# STM32Fx.net
KiCad netlist of a schematic drawn in Altium Designer
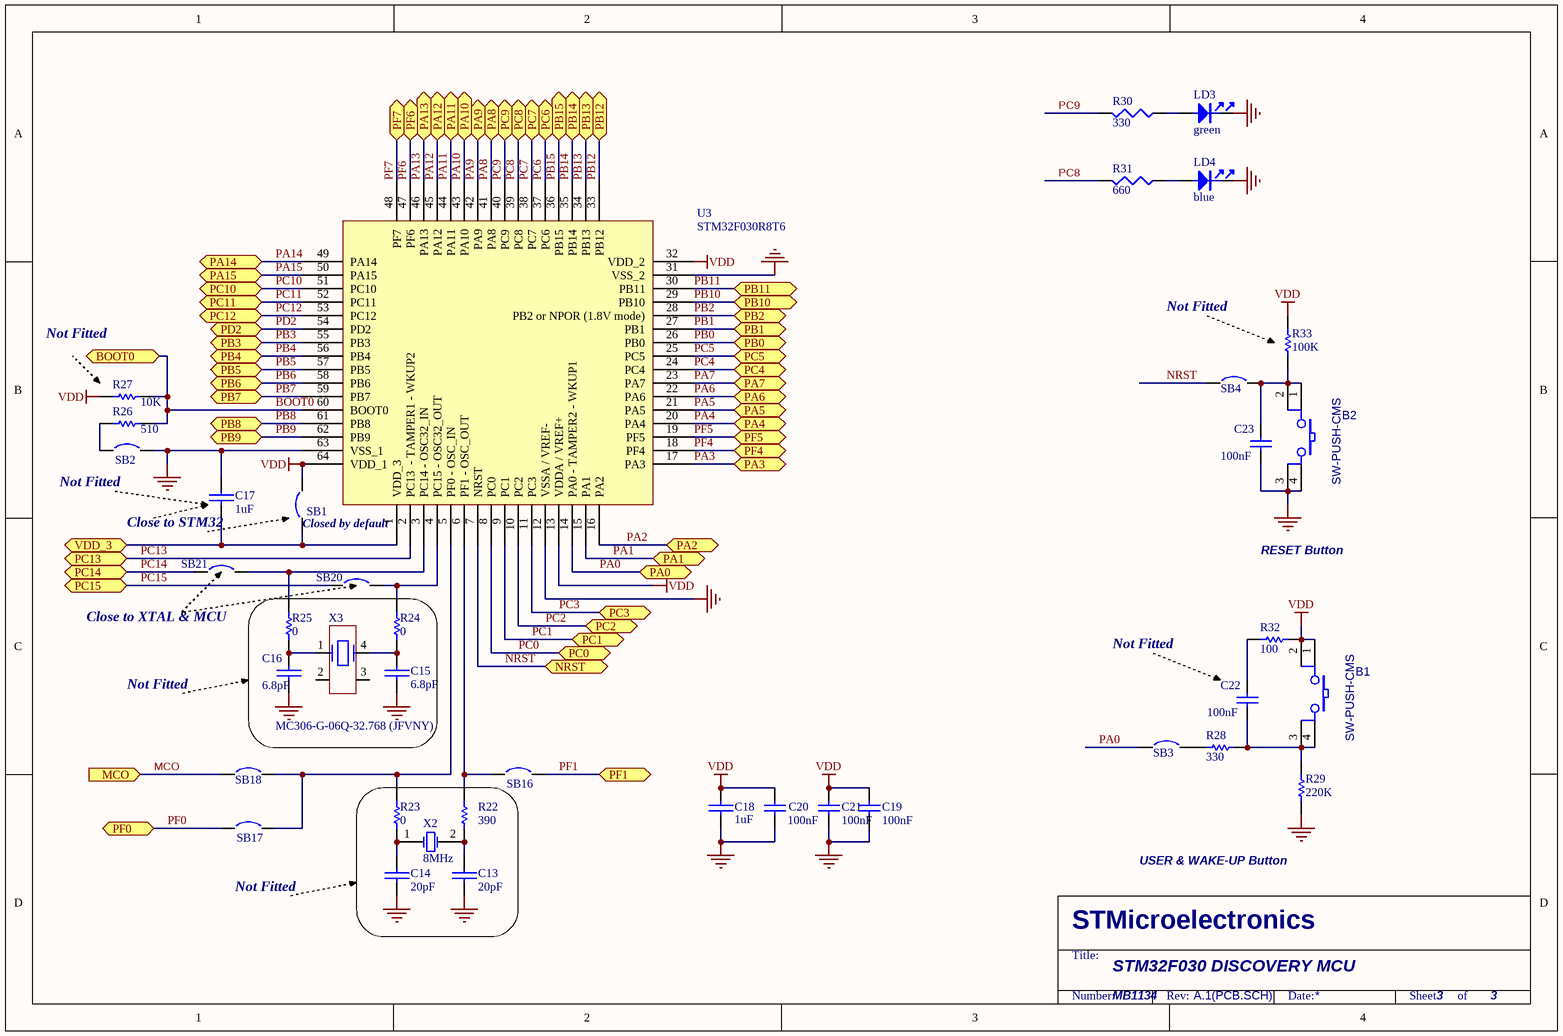
[diagram p0: STM32Fx.SchDoc]

(export (version "E")
  (design (tool "Eeschema 10.0.6"))
  (components
    (comp (ref "B1")
      (value "SW-PUSH-CMS")
      (footprint "BP1CMS")
      (description "Non-Open Push-Button 0.1A 24V")
      (libsource (lib "MB1034") (part "SW-PUSH-CMS"))
    )
    (comp (ref "B2")
      (value "SW-PUSH-CMS")
      (footprint "BP1CMS")
      (description "Non-Open Push-Button 0.1A 24V")
      (libsource (lib "MB1034") (part "SW-PUSH-CMS"))
    )
    (comp (ref "C13")
      (value "20pF")
      (footprint "0603C")
      (description "Capacitor")
      (libsource (lib "*") (part "CAP"))
    )
    (comp (ref "C14")
      (value "20pF")
      (footprint "0603C")
      (description "Capacitor")
      (libsource (lib "*") (part "CAP"))
    )
    (comp (ref "C15")
      (value "6.8pF")
      (footprint "0603C")
      (description "Capacitor")
      (libsource (lib "") (part "CAP_1"))
    )
    (comp (ref "C16")
      (value "6.8pF")
      (footprint "0603C")
      (description "Capacitor")
      (libsource (lib "") (part "CAP_1"))
    )
    (comp (ref "C17")
      (value "1uF")
      (footprint "0603C")
      (description "Capacitor")
      (libsource (lib "*") (part "CAP"))
    )
    (comp (ref "C18")
      (value "1uF")
      (footprint "0603C")
      (description "Capacitor")
      (libsource (lib "*") (part "CAP"))
    )
    (comp (ref "C19")
      (value "100nF")
      (footprint "0603C")
      (description "Capacitor")
      (fields (field (name "PUBLISHER") "Altium Limited"))
      (libsource (lib "Miscellaneous Devices") (part "Cap"))
    )
    (comp (ref "C20")
      (value "100nF")
      (footprint "0603C")
      (description "Capacitor")
      (fields (field (name "PUBLISHER") "Altium Limited"))
      (libsource (lib "Miscellaneous Devices") (part "Cap"))
    )
    (comp (ref "C21")
      (value "100nF")
      (footprint "0603C")
      (description "Capacitor")
      (fields (field (name "PUBLISHER") "Altium Limited"))
      (libsource (lib "Miscellaneous Devices") (part "Cap"))
    )
    (comp (ref "C22")
      (value "100nF")
      (footprint "0603C")
      (description "Capacitor")
      (fields (field (name "PUBLISHER") "Altium Limited"))
      (libsource (lib "Miscellaneous Devices") (part "CAP"))
    )
    (comp (ref "C23")
      (value "100nF")
      (footprint "0603C")
      (description "Capacitor")
      (fields (field (name "PUBLISHER") "Altium Limited"))
      (libsource (lib "Miscellaneous Devices") (part "CAP"))
    )
    (comp (ref "LD3") (value "green") (footprint "0603D") (libsource (lib "*") (part "PHOTO")))
    (comp (ref "LD4") (value "blue") (footprint "0603D") (libsource (lib "*") (part "PHOTO")))
    (comp (ref "R22")
      (value "390")
      (footprint "0603R")
      (description "Resistor")
      (fields (field (name "PUBLISHER") "Altium Limited"))
      (libsource (lib "Miscellaneous Devices") (part "Res1"))
    )
    (comp (ref "R23")
      (value "0")
      (footprint "0603R-GS")
      (description "Resistor")
      (fields (field (name "PUBLISHER") "Altium Limited"))
      (libsource (lib "Miscellaneous Devices") (part "Res1"))
    )
    (comp (ref "R24")
      (value "0")
      (footprint "0603R-GS")
      (description "Resistor")
      (fields (field (name "PUBLISHER") "Altium Limited"))
      (libsource (lib "Miscellaneous Devices") (part "Res1"))
    )
    (comp (ref "R25")
      (value "0")
      (footprint "0603R-GS")
      (description "Resistor")
      (fields (field (name "PUBLISHER") "Altium Limited"))
      (libsource (lib "Miscellaneous Devices") (part "Res1"))
    )
    (comp (ref "R26")
      (value "510")
      (footprint "0603R")
      (description "Resistor")
      (fields (field (name "PUBLISHER") "Altium Limited"))
      (libsource (lib "Miscellaneous Devices") (part "Res1"))
    )
    (comp (ref "R27")
      (value "10K")
      (footprint "0603R")
      (description "Resistor")
      (fields (field (name "PUBLISHER") "Altium Limited"))
      (libsource (lib "Miscellaneous Devices") (part "res1"))
    )
    (comp (ref "R28")
      (value "330")
      (footprint "0402R")
      (description "Resistor")
      (fields (field (name "PUBLISHER") "Altium Limited"))
      (libsource (lib "Miscellaneous Devices") (part "res1"))
    )
    (comp (ref "R29")
      (value "220K")
      (description "Resistor")
      (fields (field (name "PUBLISHER") "Altium Limited"))
      (libsource (lib "Miscellaneous Devices") (part "res1"))
    )
    (comp (ref "R30") (value "330") (footprint "0603R") (libsource (lib "*") (part "RES1")))
    (comp (ref "R31") (value "660") (footprint "0603R") (libsource (lib "*") (part "RES1")))
    (comp (ref "R32")
      (value "100")
      (footprint "0402R")
      (description "Resistor")
      (fields (field (name "PUBLISHER") "Altium Limited"))
      (libsource (lib "Miscellaneous Devices") (part "res1"))
    )
    (comp (ref "R33")
      (value "100K")
      (footprint "0402R")
      (description "Resistor")
      (fields (field (name "PUBLISHER") "Altium Limited"))
      (libsource (lib "Miscellaneous Devices") (part "res1"))
    )
    (comp (ref "SB1")
      (value "Circuit Breaker")
      (footprint "JP2_SMD")
      (fields (field (name "PUBLISHER") "Altium Limited"))
      (libsource (lib "MB915") (part "Circuit Breaker"))
    )
    (comp (ref "SB2")
      (value "Circuit Breaker")
      (footprint "JP2_SMD")
      (fields (field (name "PUBLISHER") "Altium Limited"))
      (libsource (lib "MB915") (part "Circuit Breaker"))
    )
    (comp (ref "SB3")
      (value "Circuit Breaker")
      (footprint "JP2_SMD")
      (fields (field (name "PUBLISHER") "Altium Limited"))
      (libsource (lib "MB915") (part "Circuit Breaker"))
    )
    (comp (ref "SB4")
      (value "Circuit Breaker")
      (footprint "JP2_SMD")
      (fields (field (name "PUBLISHER") "Altium Limited"))
      (libsource (lib "MB915") (part "Circuit Breaker"))
    )
    (comp (ref "SB16")
      (value "Circuit Breaker")
      (footprint "JP2_SMD")
      (fields (field (name "PUBLISHER") "Altium Limited"))
      (libsource (lib "MB915") (part "Circuit Breaker"))
    )
    (comp (ref "SB17")
      (value "Circuit Breaker")
      (footprint "JP2_SMD")
      (fields (field (name "PUBLISHER") "Altium Limited"))
      (libsource (lib "MB915") (part "Circuit Breaker"))
    )
    (comp (ref "SB18")
      (value "Circuit Breaker")
      (footprint "JP2_SMD")
      (fields (field (name "PUBLISHER") "Altium Limited"))
      (libsource (lib "MB915") (part "Circuit Breaker"))
    )
    (comp (ref "SB20")
      (value "Circuit Breaker")
      (footprint "JP2_SMD")
      (fields (field (name "PUBLISHER") "Altium Limited"))
      (libsource (lib "MB915") (part "Circuit Breaker"))
    )
    (comp (ref "SB21")
      (value "Circuit Breaker")
      (footprint "JP2_SMD")
      (fields (field (name "PUBLISHER") "Altium Limited"))
      (libsource (lib "MB915") (part "Circuit Breaker"))
    )
    (comp (ref "U3")
      (value "STM32F030R8T6")
      (footprint "LQFP64")
      (description "Advanced ARM based 32-bit Cortex?M0 MCU with 64 Kbytes Flash and 8 Kbytes of SRAM")
      (libsource (lib "MB1134") (part "STM32F030R8T6"))
    )
    (comp (ref "X2")
      (value "8MHz")
      (footprint "XTAL1")
      (description "Crystal Oscillator")
      (fields (field (name "PUBLISHER") "Altium Limited"))
      (libsource (lib "MCD_TOOLS") (part "XTAL"))
    )
    (comp (ref "X3")
      (value "MC306-G-06Q-32.768 (JFVNY)")
      (footprint "MC306-CRYSTAL")
      (libsource (lib "*") (part "MC306"))
    )
  )
  (nets
    (net (code "1") (name "/BOOT0") (class "Default")
      (node (ref "R26") (pin "2") (pinfunction "2_2") (pintype "passive"))
      (node (ref "R27") (pin "2") (pinfunction "2_2") (pintype "passive"))
      (node (ref "U3") (pin "60") (pinfunction "BOOT0_60") (pintype "passive"))
    )
    (net (code "2") (name "/MCO") (class "Default")
      (node (ref "SB18") (pin "1") (pinfunction "1_1") (pintype "passive"))
    )
    (net (code "3") (name "/NRST") (class "Default")
      (node (ref "SB4") (pin "1") (pinfunction "1_1") (pintype "passive"))
      (node (ref "U3") (pin "7") (pinfunction "NRST_7") (pintype "passive"))
    )
    (net (code "4") (name "/PA0") (class "Default")
      (node (ref "SB3") (pin "1") (pinfunction "1_1") (pintype "passive"))
      (node (ref "U3") (pin "14") (pinfunction "PA0_-_TAMPER2_-_WKUP1_14") (pintype "passive"))
    )
    (net (code "5") (name "/PA1") (class "Default")
      (node (ref "U3") (pin "15") (pinfunction "PA1_15") (pintype "passive"))
    )
    (net (code "6") (name "/PA2") (class "Default")
      (node (ref "U3") (pin "16") (pinfunction "PA2_16") (pintype "passive"))
    )
    (net (code "7") (name "/PA3") (class "Default")
      (node (ref "U3") (pin "17") (pinfunction "PA3_17") (pintype "passive"))
    )
    (net (code "8") (name "/PA4") (class "Default")
      (node (ref "U3") (pin "20") (pinfunction "PA4_20") (pintype "passive"))
    )
    (net (code "9") (name "/PA5") (class "Default")
      (node (ref "U3") (pin "21") (pinfunction "PA5_21") (pintype "passive"))
    )
    (net (code "10") (name "/PA6") (class "Default")
      (node (ref "U3") (pin "22") (pinfunction "PA6_22") (pintype "passive"))
    )
    (net (code "11") (name "/PA7") (class "Default")
      (node (ref "U3") (pin "23") (pinfunction "PA7_23") (pintype "passive"))
    )
    (net (code "12") (name "/PA8") (class "Default")
      (node (ref "U3") (pin "41") (pinfunction "PA8_41") (pintype "passive"))
    )
    (net (code "13") (name "/PA9") (class "Default")
      (node (ref "U3") (pin "42") (pinfunction "PA9_42") (pintype "passive"))
    )
    (net (code "14") (name "/PA10") (class "Default")
      (node (ref "U3") (pin "43") (pinfunction "PA10_43") (pintype "passive"))
    )
    (net (code "15") (name "/PA11") (class "Default")
      (node (ref "U3") (pin "44") (pinfunction "PA11_44") (pintype "passive"))
    )
    (net (code "16") (name "/PA12") (class "Default")
      (node (ref "U3") (pin "45") (pinfunction "PA12_45") (pintype "passive"))
    )
    (net (code "17") (name "/PA13") (class "Default")
      (node (ref "U3") (pin "46") (pinfunction "PA13_46") (pintype "passive"))
    )
    (net (code "18") (name "/PA14") (class "Default")
      (node (ref "U3") (pin "49") (pinfunction "PA14_49") (pintype "passive"))
    )
    (net (code "19") (name "/PA15") (class "Default")
      (node (ref "U3") (pin "50") (pinfunction "PA15_50") (pintype "passive"))
    )
    (net (code "20") (name "/PB0") (class "Default")
      (node (ref "U3") (pin "26") (pinfunction "PB0_26") (pintype "passive"))
    )
    (net (code "21") (name "/PB1") (class "Default")
      (node (ref "U3") (pin "27") (pinfunction "PB1_27") (pintype "passive"))
    )
    (net (code "22") (name "/PB2") (class "Default")
      (node (ref "U3") (pin "28") (pinfunction "PB2_or_NPOR_(1.8V_mode)_28") (pintype "passive"))
    )
    (net (code "23") (name "/PB3") (class "Default")
      (node (ref "U3") (pin "55") (pinfunction "PB3_55") (pintype "passive"))
    )
    (net (code "24") (name "/PB4") (class "Default")
      (node (ref "U3") (pin "56") (pinfunction "PB4_56") (pintype "passive"))
    )
    (net (code "25") (name "/PB5") (class "Default")
      (node (ref "U3") (pin "57") (pinfunction "PB5_57") (pintype "passive"))
    )
    (net (code "26") (name "/PB6") (class "Default")
      (node (ref "U3") (pin "58") (pinfunction "PB6_58") (pintype "passive"))
    )
    (net (code "27") (name "/PB7") (class "Default")
      (node (ref "U3") (pin "59") (pinfunction "PB7_59") (pintype "passive"))
    )
    (net (code "28") (name "/PB8") (class "Default")
      (node (ref "U3") (pin "61") (pinfunction "PB8_61") (pintype "passive"))
    )
    (net (code "29") (name "/PB9") (class "Default")
      (node (ref "U3") (pin "62") (pinfunction "PB9_62") (pintype "passive"))
    )
    (net (code "30") (name "/PB10") (class "Default")
      (node (ref "U3") (pin "29") (pinfunction "PB10_29") (pintype "passive"))
    )
    (net (code "31") (name "/PB11") (class "Default")
      (node (ref "U3") (pin "30") (pinfunction "PB11_30") (pintype "passive"))
    )
    (net (code "32") (name "/PB12") (class "Default")
      (node (ref "U3") (pin "33") (pinfunction "PB12_33") (pintype "passive"))
    )
    (net (code "33") (name "/PB13") (class "Default")
      (node (ref "U3") (pin "34") (pinfunction "PB13_34") (pintype "passive"))
    )
    (net (code "34") (name "/PB14") (class "Default")
      (node (ref "U3") (pin "35") (pinfunction "PB14_35") (pintype "passive"))
    )
    (net (code "35") (name "/PB15") (class "Default")
      (node (ref "U3") (pin "36") (pinfunction "PB15_36") (pintype "passive"))
    )
    (net (code "36") (name "/PC0") (class "Default")
      (node (ref "U3") (pin "8") (pinfunction "PC0_8") (pintype "passive"))
    )
    (net (code "37") (name "/PC1") (class "Default")
      (node (ref "U3") (pin "9") (pinfunction "PC1_9") (pintype "passive"))
    )
    (net (code "38") (name "/PC2") (class "Default")
      (node (ref "U3") (pin "10") (pinfunction "PC2_10") (pintype "passive"))
    )
    (net (code "39") (name "/PC3") (class "Default")
      (node (ref "U3") (pin "11") (pinfunction "PC3_11") (pintype "passive"))
    )
    (net (code "40") (name "/PC4") (class "Default")
      (node (ref "U3") (pin "24") (pinfunction "PC4_24") (pintype "passive"))
    )
    (net (code "41") (name "/PC5") (class "Default")
      (node (ref "U3") (pin "25") (pinfunction "PC5_25") (pintype "passive"))
    )
    (net (code "42") (name "/PC6") (class "Default")
      (node (ref "U3") (pin "37") (pinfunction "PC6_37") (pintype "passive"))
    )
    (net (code "43") (name "/PC7") (class "Default")
      (node (ref "U3") (pin "38") (pinfunction "PC7_38") (pintype "passive"))
    )
    (net (code "44") (name "/PC8") (class "Default")
      (node (ref "R31") (pin "2") (pinfunction "2_2") (pintype "passive"))
      (node (ref "U3") (pin "39") (pinfunction "PC8_39") (pintype "passive"))
    )
    (net (code "45") (name "/PC9") (class "Default")
      (node (ref "R30") (pin "2") (pinfunction "2_2") (pintype "passive"))
      (node (ref "U3") (pin "40") (pinfunction "PC9_40") (pintype "passive"))
    )
    (net (code "46") (name "/PC10") (class "Default")
      (node (ref "U3") (pin "51") (pinfunction "PC10_51") (pintype "passive"))
    )
    (net (code "47") (name "/PC11") (class "Default")
      (node (ref "U3") (pin "52") (pinfunction "PC11_52") (pintype "passive"))
    )
    (net (code "48") (name "/PC12") (class "Default")
      (node (ref "U3") (pin "53") (pinfunction "PC12_53") (pintype "passive"))
    )
    (net (code "49") (name "/PC13") (class "Default")
      (node (ref "U3") (pin "2") (pinfunction "PC13__-_TAMPER1_-_WKUP2_2") (pintype "passive"))
    )
    (net (code "50") (name "/PC14") (class "Default")
      (node (ref "SB21") (pin "1") (pinfunction "1_1") (pintype "passive"))
    )
    (net (code "51") (name "/PC15") (class "Default")
      (node (ref "SB20") (pin "1") (pinfunction "1_1") (pintype "passive"))
    )
    (net (code "52") (name "/PD2") (class "Default")
      (node (ref "U3") (pin "54") (pinfunction "PD2_54") (pintype "passive"))
    )
    (net (code "53") (name "/PF0") (class "Default")
      (node (ref "SB17") (pin "1") (pinfunction "1_1") (pintype "passive"))
    )
    (net (code "54") (name "/PF1") (class "Default")
      (node (ref "SB16") (pin "2") (pinfunction "2_2") (pintype "passive"))
    )
    (net (code "55") (name "/PF4") (class "Default")
      (node (ref "U3") (pin "18") (pinfunction "PF4_18") (pintype "passive"))
    )
    (net (code "56") (name "/PF5") (class "Default")
      (node (ref "U3") (pin "19") (pinfunction "PF5_19") (pintype "passive"))
    )
    (net (code "57") (name "/PF6") (class "Default")
      (node (ref "U3") (pin "47") (pinfunction "PF6_47") (pintype "passive"))
    )
    (net (code "58") (name "/PF7") (class "Default")
      (node (ref "U3") (pin "48") (pinfunction "PF7_48") (pintype "passive"))
    )
    (net (code "59") (name "/VDD_3") (class "Default")
      (node (ref "C17") (pin "2") (pinfunction "2_2") (pintype "passive"))
      (node (ref "SB1") (pin "1") (pinfunction "1_1") (pintype "passive"))
      (node (ref "U3") (pin "1") (pinfunction "VDD_3_1") (pintype "passive"))
    )
    (net (code "60") (name "GND") (class "Default")
      (node (ref "B2") (pin "3") (pinfunction "3_3") (pintype "passive"))
      (node (ref "B2") (pin "4") (pinfunction "4_4") (pintype "passive"))
      (node (ref "C13") (pin "2") (pinfunction "2_2") (pintype "passive"))
      (node (ref "C14") (pin "2") (pinfunction "2_2") (pintype "passive"))
      (node (ref "C15") (pin "2") (pinfunction "2_2") (pintype "passive"))
      (node (ref "C16") (pin "2") (pinfunction "2_2") (pintype "passive"))
      (node (ref "C17") (pin "1") (pinfunction "1_1") (pintype "passive"))
      (node (ref "C18") (pin "2") (pinfunction "2_2") (pintype "passive"))
      (node (ref "C19") (pin "2") (pinfunction "2_2") (pintype "passive"))
      (node (ref "C20") (pin "2") (pinfunction "2_2") (pintype "passive"))
      (node (ref "C21") (pin "2") (pinfunction "2_2") (pintype "passive"))
      (node (ref "C23") (pin "1") (pinfunction "1_1") (pintype "passive"))
      (node (ref "LD3") (pin "2") (pintype "passive"))
      (node (ref "LD4") (pin "2") (pintype "passive"))
      (node (ref "R29") (pin "1") (pinfunction "1_1") (pintype "passive"))
      (node (ref "SB2") (pin "2") (pinfunction "2_2") (pintype "passive"))
      (node (ref "U3") (pin "12") (pinfunction "VSSA_/_VREF-_12") (pintype "passive"))
      (node (ref "U3") (pin "31") (pinfunction "VSS_2_31") (pintype "passive"))
      (node (ref "U3") (pin "63") (pinfunction "VSS_1_63") (pintype "passive"))
    )
    (net (code "61") (name "Net-(B1-Pad3)") (class "Default")
      (node (ref "B1") (pin "3") (pinfunction "3_3") (pintype "passive"))
      (node (ref "B1") (pin "4") (pinfunction "4_4") (pintype "passive"))
      (node (ref "C22") (pin "1") (pinfunction "1_1") (pintype "passive"))
      (node (ref "R28") (pin "2") (pinfunction "2_2") (pintype "passive"))
      (node (ref "R29") (pin "2") (pinfunction "2_2") (pintype "passive"))
    )
    (net (code "62") (name "Net-(B2-Pad1)") (class "Default")
      (node (ref "B2") (pin "1") (pinfunction "1_1") (pintype "passive"))
      (node (ref "B2") (pin "2") (pinfunction "2_2") (pintype "passive"))
      (node (ref "C23") (pin "2") (pinfunction "2_2") (pintype "passive"))
      (node (ref "R33") (pin "1") (pinfunction "1_1") (pintype "passive"))
      (node (ref "SB4") (pin "2") (pinfunction "2_2") (pintype "passive"))
    )
    (net (code "63") (name "Net-(C15-Pad1)") (class "Default")
      (node (ref "C15") (pin "1") (pinfunction "1_1") (pintype "passive"))
      (node (ref "R24") (pin "1") (pinfunction "1_1") (pintype "passive"))
      (node (ref "X3") (pin "4") (pinfunction "4_4") (pintype "passive"))
    )
    (net (code "64") (name "Net-(C16-Pad1)") (class "Default")
      (node (ref "C16") (pin "1") (pinfunction "1_1") (pintype "passive"))
      (node (ref "R25") (pin "1") (pinfunction "1_1") (pintype "passive"))
      (node (ref "X3") (pin "1") (pinfunction "1_1") (pintype "passive"))
    )
    (net (code "65") (name "Net-(C22-Pad2)") (class "Default")
      (node (ref "C22") (pin "2") (pinfunction "2_2") (pintype "passive"))
      (node (ref "R32") (pin "1") (pinfunction "1_1") (pintype "passive"))
    )
    (net (code "66") (name "Net-(LD3-Pad1)") (class "Default")
      (node (ref "LD3") (pin "1") (pintype "passive"))
      (node (ref "R30") (pin "1") (pinfunction "1_1") (pintype "passive"))
    )
    (net (code "67") (name "Net-(LD4-Pad1)") (class "Default")
      (node (ref "LD4") (pin "1") (pintype "passive"))
      (node (ref "R31") (pin "1") (pinfunction "1_1") (pintype "passive"))
    )
    (net (code "68") (name "Net-(R26-Pad1)") (class "Default")
      (node (ref "R26") (pin "1") (pinfunction "1_1") (pintype "passive"))
      (node (ref "SB2") (pin "1") (pinfunction "1_1") (pintype "passive"))
    )
    (net (code "69") (name "Net-(R28-Pad1)") (class "Default")
      (node (ref "R28") (pin "1") (pinfunction "1_1") (pintype "passive"))
      (node (ref "SB3") (pin "2") (pinfunction "2_2") (pintype "passive"))
    )
    (net (code "70") (name "Net-(U3-PC14_-_OSC32_IN)") (class "Default")
      (node (ref "R25") (pin "2") (pinfunction "2_2") (pintype "passive"))
      (node (ref "SB21") (pin "2") (pinfunction "2_2") (pintype "passive"))
      (node (ref "U3") (pin "3") (pinfunction "PC14_-_OSC32_IN_3") (pintype "passive"))
    )
    (net (code "71") (name "Net-(U3-PC15_-_OSC32_OUT)") (class "Default")
      (node (ref "R24") (pin "2") (pinfunction "2_2") (pintype "passive"))
      (node (ref "SB20") (pin "2") (pinfunction "2_2") (pintype "passive"))
      (node (ref "U3") (pin "4") (pinfunction "PC15_-_OSC32_OUT_4") (pintype "passive"))
    )
    (net (code "72") (name "Net-(U3-PF0_-_OSC_IN)") (class "Default")
      (node (ref "R23") (pin "2") (pinfunction "2_2") (pintype "passive"))
      (node (ref "SB17") (pin "2") (pinfunction "2_2") (pintype "passive"))
      (node (ref "SB18") (pin "2") (pinfunction "2_2") (pintype "passive"))
      (node (ref "U3") (pin "5") (pinfunction "PF0_-_OSC_IN_5") (pintype "passive"))
    )
    (net (code "73") (name "Net-(U3-PF1_-_OSC_OUT)") (class "Default")
      (node (ref "R22") (pin "1") (pinfunction "1_1") (pintype "passive"))
      (node (ref "SB16") (pin "1") (pinfunction "1_1") (pintype "passive"))
      (node (ref "U3") (pin "6") (pinfunction "PF1_-_OSC_OUT_6") (pintype "passive"))
    )
    (net (code "74") (name "Net-(X2-OSC1)") (class "Default")
      (node (ref "C14") (pin "1") (pinfunction "1_1") (pintype "passive"))
      (node (ref "R23") (pin "1") (pinfunction "1_1") (pintype "passive"))
      (node (ref "X2") (pin "1") (pinfunction "OSC1_1") (pintype "passive"))
    )
    (net (code "75") (name "Net-(X2-OSC2)") (class "Default")
      (node (ref "C13") (pin "1") (pinfunction "1_1") (pintype "passive"))
      (node (ref "R22") (pin "2") (pinfunction "2_2") (pintype "passive"))
      (node (ref "X2") (pin "2") (pinfunction "OSC2_2") (pintype "passive"))
    )
    (net (code "76") (name "VDD") (class "Default")
      (node (ref "B1") (pin "1") (pinfunction "1_1") (pintype "passive"))
      (node (ref "B1") (pin "2") (pinfunction "2_2") (pintype "passive"))
      (node (ref "C18") (pin "1") (pinfunction "1_1") (pintype "passive"))
      (node (ref "C19") (pin "1") (pinfunction "1_1") (pintype "passive"))
      (node (ref "C20") (pin "1") (pinfunction "1_1") (pintype "passive"))
      (node (ref "C21") (pin "1") (pinfunction "1_1") (pintype "passive"))
      (node (ref "R27") (pin "1") (pinfunction "1_1") (pintype "passive"))
      (node (ref "R32") (pin "2") (pinfunction "2_2") (pintype "passive"))
      (node (ref "R33") (pin "2") (pinfunction "2_2") (pintype "passive"))
      (node (ref "SB1") (pin "2") (pinfunction "2_2") (pintype "passive"))
      (node (ref "U3") (pin "13") (pinfunction "VDDA_/_VREF+_13") (pintype "passive"))
      (node (ref "U3") (pin "32") (pinfunction "VDD_2_32") (pintype "passive"))
      (node (ref "U3") (pin "64") (pinfunction "VDD_1_64") (pintype "passive"))
    )
    (net (code "77") (name "unconnected-(X3-Pad2)") (class "Default")
      (node (ref "X3") (pin "2") (pinfunction "2_2") (pintype "passive"))
    )
    (net (code "78") (name "unconnected-(X3-Pad3)") (class "Default")
      (node (ref "X3") (pin "3") (pinfunction "3_3") (pintype "passive"))
    )
  )
)
